# same51-dev.net
KiCad netlist of a schematic drawn in EAGLE
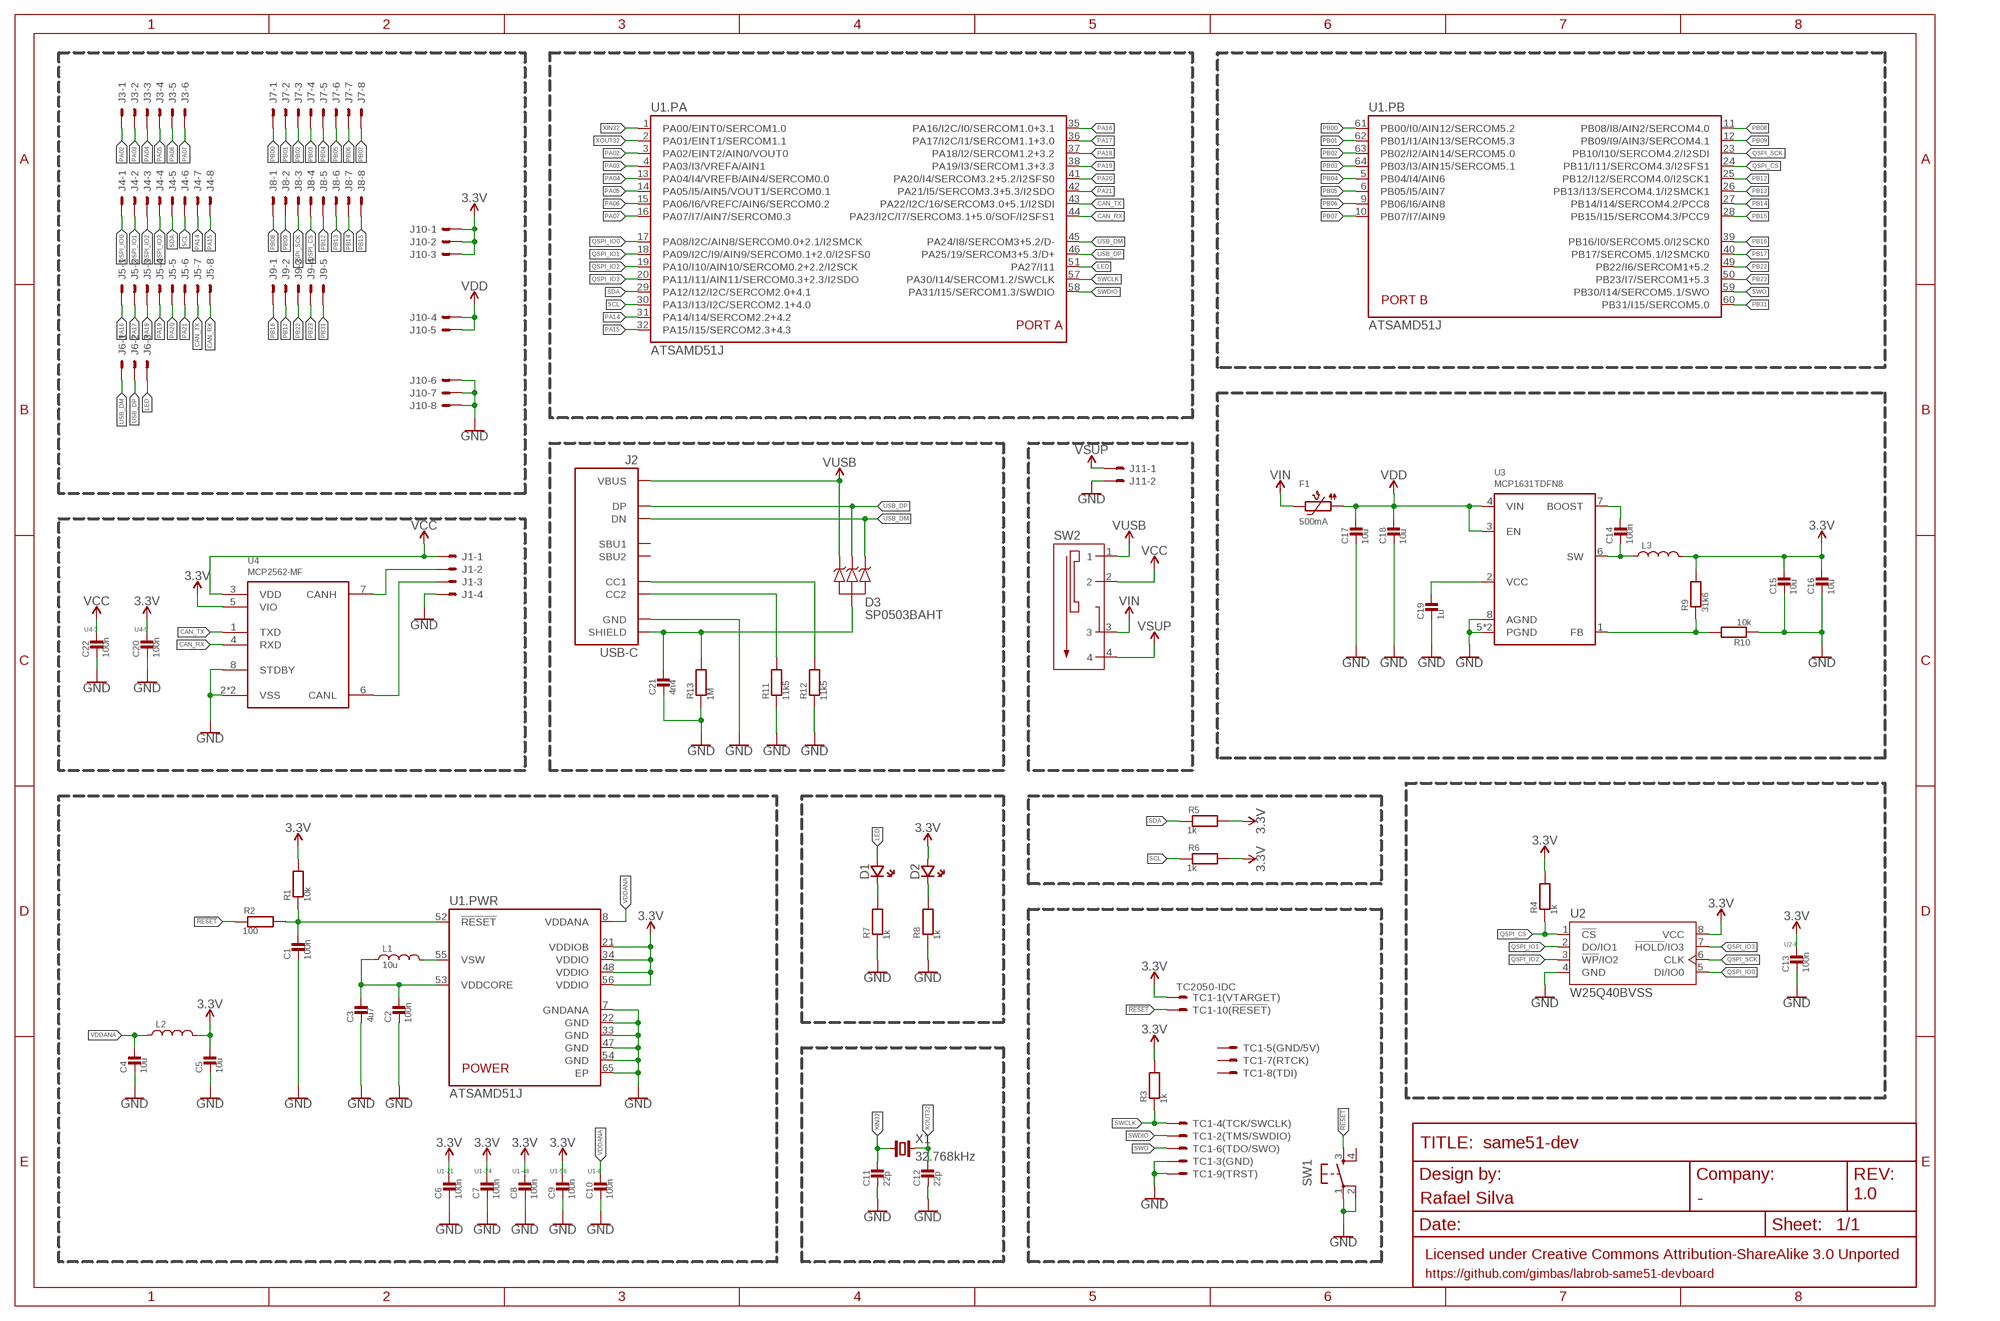
[diagram p0: schematic, sheet 1]

(export (version "E")
  (design (tool "Eeschema 10.0.6"))
  (components
    (comp (ref "C1")
      (value "100n")
      (footprint "eagle-import:0603_WAVE")
      (libsource (lib "eagle-import") (part "MLCC0603"))
    )
    (comp (ref "C2")
      (value "100n")
      (footprint "eagle-import:0603_WAVE")
      (libsource (lib "eagle-import") (part "MLCC0603"))
    )
    (comp (ref "C3")
      (value "4u7")
      (footprint "eagle-import:0603_WAVE")
      (libsource (lib "eagle-import") (part "MLCC0603"))
    )
    (comp (ref "C4")
      (value "10u")
      (footprint "eagle-import:0603_WAVE")
      (libsource (lib "eagle-import") (part "MLCC0603"))
    )
    (comp (ref "C5")
      (value "10u")
      (footprint "eagle-import:0603_WAVE")
      (libsource (lib "eagle-import") (part "MLCC0603"))
    )
    (comp (ref "C6")
      (value "100n")
      (footprint "eagle-import:0603_WAVE")
      (libsource (lib "eagle-import") (part "MLCC0603"))
    )
    (comp (ref "C7")
      (value "100n")
      (footprint "eagle-import:0603_WAVE")
      (libsource (lib "eagle-import") (part "MLCC0603"))
    )
    (comp (ref "C8")
      (value "100n")
      (footprint "eagle-import:0603_WAVE")
      (libsource (lib "eagle-import") (part "MLCC0603"))
    )
    (comp (ref "C9")
      (value "100n")
      (footprint "eagle-import:0603_WAVE")
      (libsource (lib "eagle-import") (part "MLCC0603"))
    )
    (comp (ref "C10")
      (value "100n")
      (footprint "eagle-import:0603_WAVE")
      (libsource (lib "eagle-import") (part "MLCC0603"))
    )
    (comp (ref "C11")
      (value "22p")
      (footprint "eagle-import:0603_WAVE")
      (libsource (lib "eagle-import") (part "MLCC0603"))
    )
    (comp (ref "C12")
      (value "22p")
      (footprint "eagle-import:0603_WAVE")
      (libsource (lib "eagle-import") (part "MLCC0603"))
    )
    (comp (ref "C13")
      (value "100n")
      (footprint "eagle-import:0603_WAVE")
      (libsource (lib "eagle-import") (part "MLCC0603"))
    )
    (comp (ref "C14")
      (value "100n")
      (footprint "eagle-import:0603_WAVE")
      (libsource (lib "eagle-import") (part "MLCC0603"))
    )
    (comp (ref "C15")
      (value "10u")
      (footprint "eagle-import:0603_WAVE")
      (libsource (lib "eagle-import") (part "MLCC0603"))
    )
    (comp (ref "C16")
      (value "10u")
      (footprint "eagle-import:0603_WAVE")
      (libsource (lib "eagle-import") (part "MLCC0603"))
    )
    (comp (ref "C17")
      (value "10u")
      (footprint "eagle-import:0603_WAVE")
      (libsource (lib "eagle-import") (part "MLCC0603"))
    )
    (comp (ref "C18")
      (value "10u")
      (footprint "eagle-import:0603_WAVE")
      (libsource (lib "eagle-import") (part "MLCC0603"))
    )
    (comp (ref "C19")
      (value "1u")
      (footprint "eagle-import:0603_WAVE")
      (libsource (lib "eagle-import") (part "MLCC0603"))
    )
    (comp (ref "C20")
      (value "100n")
      (footprint "eagle-import:0603_WAVE")
      (libsource (lib "eagle-import") (part "MLCC0603"))
    )
    (comp (ref "C21")
      (value "4n4")
      (footprint "eagle-import:0603_WAVE")
      (libsource (lib "eagle-import") (part "MLCC0603"))
    )
    (comp (ref "C22")
      (value "100n")
      (footprint "eagle-import:0603_WAVE")
      (libsource (lib "eagle-import") (part "MLCC0603"))
    )
    (comp (ref "D1")
      (value "LED0603")
      (footprint "eagle-import:CHIPLED_0603")
      (libsource (lib "eagle-import") (part "LED0603"))
    )
    (comp (ref "D2")
      (value "LED0603")
      (footprint "eagle-import:CHIPLED_0603")
      (libsource (lib "eagle-import") (part "LED0603"))
    )
    (comp (ref "D3")
      (value "SP0503BAHT")
      (footprint "eagle-import:SOT143")
      (libsource (lib "eagle-import") (part "SP0503BAHT"))
    )
    (comp (ref "F1")
      (value "500mA")
      (footprint "eagle-import:0805")
      (libsource (lib "eagle-import") (part "PTC0805"))
    )
    (comp (ref "J1")
      (value "4")
      (footprint "eagle-import:1X4_2.54")
      (libsource (lib "eagle-import") (part "4"))
    )
    (comp (ref "J2")
      (value "USB-C")
      (footprint "eagle-import:USB-C")
      (libsource (lib "eagle-import") (part "USB-C"))
    )
    (comp (ref "J3")
      (value "6")
      (footprint "eagle-import:1X6_2.54")
      (libsource (lib "eagle-import") (part "6"))
    )
    (comp (ref "J4")
      (value "8")
      (footprint "eagle-import:1X8_2.54")
      (libsource (lib "eagle-import") (part "8"))
    )
    (comp (ref "J5")
      (value "8")
      (footprint "eagle-import:1X8_2.54")
      (libsource (lib "eagle-import") (part "8"))
    )
    (comp (ref "J6")
      (value "3")
      (footprint "eagle-import:1X3_2.54")
      (libsource (lib "eagle-import") (part "3"))
    )
    (comp (ref "J7")
      (value "8")
      (footprint "eagle-import:1X8_2.54")
      (libsource (lib "eagle-import") (part "8"))
    )
    (comp (ref "J8")
      (value "8")
      (footprint "eagle-import:1X8_2.54")
      (libsource (lib "eagle-import") (part "8"))
    )
    (comp (ref "J9")
      (value "5")
      (footprint "eagle-import:1X5_2.54")
      (libsource (lib "eagle-import") (part "5"))
    )
    (comp (ref "J10")
      (value "8")
      (footprint "eagle-import:1X8_2.54")
      (libsource (lib "eagle-import") (part "8"))
    )
    (comp (ref "J11")
      (value "2")
      (footprint "eagle-import:2X1_2.54")
      (libsource (lib "eagle-import") (part "2"))
    )
    (comp (ref "L1")
      (value "10u")
      (footprint "eagle-import:_0806")
      (libsource (lib "eagle-import") (part "INDUCTOR_NC_0806"))
    )
    (comp (ref "L2")
      (value "INDUCTOR_NC_0603")
      (footprint "eagle-import:_0603")
      (libsource (lib "eagle-import") (part "INDUCTOR_NC_0603"))
    )
    (comp (ref "L3")
      (value "INDUCTOR_NC_0806")
      (footprint "eagle-import:_0806")
      (libsource (lib "eagle-import") (part "INDUCTOR_NC_0806"))
    )
    (comp (ref "R1")
      (value "10k")
      (footprint "eagle-import:0603_WAVE")
      (libsource (lib "eagle-import") (part "RESISTOR0603"))
    )
    (comp (ref "R2")
      (value "100")
      (footprint "eagle-import:0603_WAVE")
      (libsource (lib "eagle-import") (part "RESISTOR0603"))
    )
    (comp (ref "R3")
      (value "1k")
      (footprint "eagle-import:0603_WAVE")
      (libsource (lib "eagle-import") (part "RESISTOR0603"))
    )
    (comp (ref "R4")
      (value "1k")
      (footprint "eagle-import:0603_WAVE")
      (libsource (lib "eagle-import") (part "RESISTOR0603"))
    )
    (comp (ref "R5")
      (value "1k")
      (footprint "eagle-import:0603_WAVE")
      (libsource (lib "eagle-import") (part "RESISTOR0603"))
    )
    (comp (ref "R6")
      (value "1k")
      (footprint "eagle-import:0603_WAVE")
      (libsource (lib "eagle-import") (part "RESISTOR0603"))
    )
    (comp (ref "R7")
      (value "1k")
      (footprint "eagle-import:0603_WAVE")
      (libsource (lib "eagle-import") (part "RESISTOR0603"))
    )
    (comp (ref "R8")
      (value "1k")
      (footprint "eagle-import:0603_WAVE")
      (libsource (lib "eagle-import") (part "RESISTOR0603"))
    )
    (comp (ref "R9")
      (value "31k6")
      (footprint "eagle-import:0603_WAVE")
      (libsource (lib "eagle-import") (part "RESISTOR0603"))
    )
    (comp (ref "R10")
      (value "10k")
      (footprint "eagle-import:0603_WAVE")
      (libsource (lib "eagle-import") (part "RESISTOR0603"))
    )
    (comp (ref "R11")
      (value "11k5")
      (footprint "eagle-import:0603_WAVE")
      (libsource (lib "eagle-import") (part "RESISTOR0603"))
    )
    (comp (ref "R12")
      (value "11k5")
      (footprint "eagle-import:0603_WAVE")
      (libsource (lib "eagle-import") (part "RESISTOR0603"))
    )
    (comp (ref "R13")
      (value "1M")
      (footprint "eagle-import:0603_WAVE")
      (libsource (lib "eagle-import") (part "RESISTOR0603"))
    )
    (comp (ref "SW1")
      (value "PUSH_BUTTON3X4X2")
      (footprint "eagle-import:3X4X2")
      (libsource (lib "eagle-import") (part "PUSH_BUTTON3X4X2"))
    )
    (comp (ref "SW2")
      (value "MSK-13C01")
      (footprint "eagle-import:MSK-13C01")
      (libsource (lib "eagle-import") (part "MSK-13C01"))
    )
    (comp (ref "TC1")
      (value "TC2050-IDC")
      (footprint "eagle-import:TC2050-IDC")
      (libsource (lib "eagle-import") (part "TC2050-IDC"))
    )
    (comp (ref "U1")
      (value "ATSAMD51J")
      (footprint "eagle-import:VQFN64")
      (libsource (lib "eagle-import") (part "ATSAMD51J"))
    )
    (comp (ref "U2")
      (value "W25Q40BVSS")
      (footprint "eagle-import:SO08-SS")
      (libsource (lib "eagle-import") (part "W25Q40BVSS"))
    )
    (comp (ref "U3")
      (value "MCP1631TDFN8")
      (footprint "eagle-import:TDFN8")
      (libsource (lib "eagle-import") (part "MCP1631TDFN8"))
    )
    (comp (ref "U4")
      (value "MCP2562-MF")
      (footprint "eagle-import:DFN8")
      (libsource (lib "eagle-import") (part "MCP2562-MF"))
    )
    (comp (ref "X1")
      (value "32.768kHz")
      (footprint "eagle-import:2-SMD-3215")
      (libsource (lib "eagle-import") (part "CRYSTAL2-SMD-3215"))
    )
  )
  (nets
    (net (code "1") (name "/~{RESET}") (class "Default")
      (node (ref "R2") (pin "P$1") (pinfunction "P$1_P$1") (pintype "bidirectional"))
      (node (ref "SW1") (pin "3") (pinfunction "4_3") (pintype "passive"))
      (node (ref "TC1") (pin "10") (pinfunction "S_10") (pintype "passive"))
    )
    (net (code "2") (name "3.3V") (class "Default")
      (node (ref "C13") (pin "P$1") (pinfunction "P$1_P$1") (pintype "bidirectional"))
      (node (ref "C15") (pin "P$1") (pinfunction "P$1_P$1") (pintype "bidirectional"))
      (node (ref "C16") (pin "P$1") (pinfunction "P$1_P$1") (pintype "bidirectional"))
      (node (ref "C20") (pin "P$1") (pinfunction "P$1_P$1") (pintype "bidirectional"))
      (node (ref "C5") (pin "P$1") (pinfunction "P$1_P$1") (pintype "bidirectional"))
      (node (ref "C6") (pin "P$1") (pinfunction "P$1_P$1") (pintype "bidirectional"))
      (node (ref "C7") (pin "P$1") (pinfunction "P$1_P$1") (pintype "bidirectional"))
      (node (ref "C8") (pin "P$1") (pinfunction "P$1_P$1") (pintype "bidirectional"))
      (node (ref "C9") (pin "P$1") (pinfunction "P$1_P$1") (pintype "bidirectional"))
      (node (ref "D2") (pin "A") (pinfunction "AN_A") (pintype "bidirectional"))
      (node (ref "J10") (pin "1") (pinfunction "S_1") (pintype "passive"))
      (node (ref "J10") (pin "2") (pinfunction "S_2") (pintype "passive"))
      (node (ref "J10") (pin "3") (pinfunction "S_3") (pintype "passive"))
      (node (ref "L2") (pin "2") (pinfunction "P$2_2") (pintype "bidirectional"))
      (node (ref "L3") (pin "2") (pinfunction "P$2_2") (pintype "bidirectional"))
      (node (ref "R1") (pin "P$2") (pinfunction "P$2_P$2") (pintype "bidirectional"))
      (node (ref "R3") (pin "P$2") (pinfunction "P$2_P$2") (pintype "bidirectional"))
      (node (ref "R4") (pin "P$2") (pinfunction "P$2_P$2") (pintype "bidirectional"))
      (node (ref "R5") (pin "P$2") (pinfunction "P$2_P$2") (pintype "bidirectional"))
      (node (ref "R6") (pin "P$2") (pinfunction "P$2_P$2") (pintype "bidirectional"))
      (node (ref "R9") (pin "P$2") (pinfunction "P$2_P$2") (pintype "bidirectional"))
      (node (ref "TC1") (pin "1") (pinfunction "S_1") (pintype "passive"))
      (node (ref "U1") (pin "21") (pinfunction "VDDIOB_21") (pintype "bidirectional"))
      (node (ref "U1") (pin "34") (pinfunction "VDDIO_34") (pintype "bidirectional"))
      (node (ref "U1") (pin "48") (pinfunction "VDDIO_48") (pintype "bidirectional"))
      (node (ref "U1") (pin "56") (pinfunction "VDDIO_56") (pintype "bidirectional"))
      (node (ref "U2") (pin "8") (pinfunction "VCC_8") (pintype "power_in"))
      (node (ref "U4") (pin "5") (pinfunction "VIO_5") (pintype "power_in"))
    )
    (net (code "3") (name "CAN_RX") (class "Default")
      (node (ref "J5") (pin "8") (pinfunction "S_8") (pintype "passive"))
      (node (ref "U1") (pin "44") (pinfunction "PA23/I2C/I7/SERCOM3.1+5.0/SOF/I2SFS1_44") (pintype "bidirectional"))
      (node (ref "U4") (pin "4") (pinfunction "RXD_4") (pintype "bidirectional"))
    )
    (net (code "4") (name "CAN_TX") (class "Default")
      (node (ref "J5") (pin "7") (pinfunction "S_7") (pintype "passive"))
      (node (ref "U1") (pin "43") (pinfunction "PA22/I2C/16/SERCOM3.0+5.1/I2SDI_43") (pintype "bidirectional"))
      (node (ref "U4") (pin "1") (pinfunction "TXD_1") (pintype "bidirectional"))
    )
    (net (code "5") (name "GND") (class "Default")
      (node (ref "C1") (pin "P$2") (pinfunction "P$2_P$2") (pintype "bidirectional"))
      (node (ref "C10") (pin "P$2") (pinfunction "P$2_P$2") (pintype "bidirectional"))
      (node (ref "C11") (pin "P$2") (pinfunction "P$2_P$2") (pintype "bidirectional"))
      (node (ref "C12") (pin "P$2") (pinfunction "P$2_P$2") (pintype "bidirectional"))
      (node (ref "C13") (pin "P$2") (pinfunction "P$2_P$2") (pintype "bidirectional"))
      (node (ref "C15") (pin "P$2") (pinfunction "P$2_P$2") (pintype "bidirectional"))
      (node (ref "C16") (pin "P$2") (pinfunction "P$2_P$2") (pintype "bidirectional"))
      (node (ref "C17") (pin "P$2") (pinfunction "P$2_P$2") (pintype "bidirectional"))
      (node (ref "C18") (pin "P$2") (pinfunction "P$2_P$2") (pintype "bidirectional"))
      (node (ref "C19") (pin "P$2") (pinfunction "P$2_P$2") (pintype "bidirectional"))
      (node (ref "C2") (pin "P$2") (pinfunction "P$2_P$2") (pintype "bidirectional"))
      (node (ref "C20") (pin "P$2") (pinfunction "P$2_P$2") (pintype "bidirectional"))
      (node (ref "C21") (pin "P$2") (pinfunction "P$2_P$2") (pintype "bidirectional"))
      (node (ref "C22") (pin "P$2") (pinfunction "P$2_P$2") (pintype "bidirectional"))
      (node (ref "C3") (pin "P$2") (pinfunction "P$2_P$2") (pintype "bidirectional"))
      (node (ref "C4") (pin "P$2") (pinfunction "P$2_P$2") (pintype "bidirectional"))
      (node (ref "C5") (pin "P$2") (pinfunction "P$2_P$2") (pintype "bidirectional"))
      (node (ref "C6") (pin "P$2") (pinfunction "P$2_P$2") (pintype "bidirectional"))
      (node (ref "C7") (pin "P$2") (pinfunction "P$2_P$2") (pintype "bidirectional"))
      (node (ref "C8") (pin "P$2") (pinfunction "P$2_P$2") (pintype "bidirectional"))
      (node (ref "C9") (pin "P$2") (pinfunction "P$2_P$2") (pintype "bidirectional"))
      (node (ref "J1") (pin "4") (pinfunction "S_4") (pintype "passive"))
      (node (ref "J10") (pin "6") (pinfunction "S_6") (pintype "passive"))
      (node (ref "J10") (pin "7") (pinfunction "S_7") (pintype "passive"))
      (node (ref "J10") (pin "8") (pinfunction "S_8") (pintype "passive"))
      (node (ref "J11") (pin "2") (pinfunction "S_2") (pintype "passive"))
      (node (ref "J2") (pin "A1/B12") (pinfunction "GND_A1/B12") (pintype "bidirectional"))
      (node (ref "J2") (pin "B1/A12") (pinfunction "GND_B1/A12") (pintype "bidirectional"))
      (node (ref "R10") (pin "P$1") (pinfunction "P$1_P$1") (pintype "bidirectional"))
      (node (ref "R11") (pin "P$1") (pinfunction "P$1_P$1") (pintype "bidirectional"))
      (node (ref "R12") (pin "P$1") (pinfunction "P$1_P$1") (pintype "bidirectional"))
      (node (ref "R13") (pin "P$1") (pinfunction "P$1_P$1") (pintype "bidirectional"))
      (node (ref "R7") (pin "P$1") (pinfunction "P$1_P$1") (pintype "bidirectional"))
      (node (ref "R8") (pin "P$1") (pinfunction "P$1_P$1") (pintype "bidirectional"))
      (node (ref "SW1") (pin "1") (pinfunction "1_1") (pintype "passive"))
      (node (ref "SW1") (pin "2") (pinfunction "2_2") (pintype "passive"))
      (node (ref "TC1") (pin "3") (pinfunction "S_3") (pintype "passive"))
      (node (ref "TC1") (pin "9") (pinfunction "S_9") (pintype "passive"))
      (node (ref "U1") (pin "22") (pinfunction "GND_22") (pintype "bidirectional"))
      (node (ref "U1") (pin "33") (pinfunction "GND_33") (pintype "bidirectional"))
      (node (ref "U1") (pin "47") (pinfunction "GND_47") (pintype "bidirectional"))
      (node (ref "U1") (pin "54") (pinfunction "GND_54") (pintype "bidirectional"))
      (node (ref "U1") (pin "65") (pinfunction "EP_65") (pintype "bidirectional"))
      (node (ref "U1") (pin "7") (pinfunction "GNDANA_7") (pintype "bidirectional"))
      (node (ref "U2") (pin "4") (pinfunction "GND_4") (pintype "power_in"))
      (node (ref "U3") (pin "5") (pinfunction "PGND_5") (pintype "bidirectional"))
      (node (ref "U3") (pin "8") (pinfunction "AGND_8") (pintype "bidirectional"))
      (node (ref "U3") (pin "9") (pinfunction "PGND_9") (pintype "bidirectional"))
      (node (ref "U4") (pin "2") (pinfunction "VSS_2") (pintype "power_in"))
      (node (ref "U4") (pin "8") (pinfunction "STDBY_8") (pintype "bidirectional"))
      (node (ref "U4") (pin "9") (pinfunction "VSS_9") (pintype "power_in"))
    )
    (net (code "6") (name "LED") (class "Default")
      (node (ref "D1") (pin "A") (pinfunction "AN_A") (pintype "bidirectional"))
      (node (ref "J6") (pin "3") (pinfunction "S_3") (pintype "passive"))
      (node (ref "U1") (pin "51") (pinfunction "PA27/I11_51") (pintype "bidirectional"))
    )
    (net (code "7") (name "Net-(C21-PadP$1)") (class "Default")
      (node (ref "C21") (pin "P$1") (pinfunction "P$1_P$1") (pintype "bidirectional"))
      (node (ref "D3") (pin "1") (pinfunction "1_1") (pintype "bidirectional"))
      (node (ref "J2") (pin "SHIELD0") (pinfunction "SHIELD_SHIELD0") (pintype "bidirectional"))
      (node (ref "J2") (pin "SHIELD1") (pinfunction "SHIELD_SHIELD1") (pintype "bidirectional"))
      (node (ref "J2") (pin "SHIELD2") (pinfunction "SHIELD_SHIELD2") (pintype "bidirectional"))
      (node (ref "J2") (pin "SHIELD3") (pinfunction "SHIELD_SHIELD3") (pintype "bidirectional"))
      (node (ref "R13") (pin "P$2") (pinfunction "P$2_P$2") (pintype "bidirectional"))
    )
    (net (code "8") (name "Net-(D1-CA)") (class "Default")
      (node (ref "D1") (pin "C") (pinfunction "CA_C") (pintype "bidirectional"))
      (node (ref "R7") (pin "P$2") (pinfunction "P$2_P$2") (pintype "bidirectional"))
    )
    (net (code "9") (name "Net-(D2-CA)") (class "Default")
      (node (ref "D2") (pin "C") (pinfunction "CA_C") (pintype "bidirectional"))
      (node (ref "R8") (pin "P$2") (pinfunction "P$2_P$2") (pintype "bidirectional"))
    )
    (net (code "10") (name "Net-(J1B-S)") (class "Default")
      (node (ref "J1") (pin "2") (pinfunction "S_2") (pintype "passive"))
      (node (ref "U4") (pin "7") (pinfunction "CANH_7") (pintype "bidirectional"))
    )
    (net (code "11") (name "Net-(J1C-S)") (class "Default")
      (node (ref "J1") (pin "3") (pinfunction "S_3") (pintype "passive"))
      (node (ref "U4") (pin "6") (pinfunction "CANL_6") (pintype "bidirectional"))
    )
    (net (code "12") (name "Net-(J2-CC1)") (class "Default")
      (node (ref "J2") (pin "A5") (pinfunction "CC1_A5") (pintype "bidirectional"))
      (node (ref "R12") (pin "P$2") (pinfunction "P$2_P$2") (pintype "bidirectional"))
    )
    (net (code "13") (name "Net-(J2-CC2)") (class "Default")
      (node (ref "J2") (pin "B5") (pinfunction "CC2_B5") (pintype "bidirectional"))
      (node (ref "R11") (pin "P$2") (pinfunction "P$2_P$2") (pintype "bidirectional"))
    )
    (net (code "14") (name "Net-(L1-P$1)") (class "Default")
      (node (ref "C2") (pin "P$1") (pinfunction "P$1_P$1") (pintype "bidirectional"))
      (node (ref "C3") (pin "P$1") (pinfunction "P$1_P$1") (pintype "bidirectional"))
      (node (ref "L1") (pin "1") (pinfunction "P$1_1") (pintype "bidirectional"))
      (node (ref "U1") (pin "53") (pinfunction "VDDCORE_53") (pintype "bidirectional"))
    )
    (net (code "15") (name "Net-(L1-P$2)") (class "Default")
      (node (ref "L1") (pin "2") (pinfunction "P$2_2") (pintype "bidirectional"))
      (node (ref "U1") (pin "55") (pinfunction "VSW_55") (pintype "bidirectional"))
    )
    (net (code "16") (name "Net-(L3-P$1)") (class "Default")
      (node (ref "C14") (pin "P$2") (pinfunction "P$2_P$2") (pintype "bidirectional"))
      (node (ref "L3") (pin "1") (pinfunction "P$1_1") (pintype "bidirectional"))
      (node (ref "U3") (pin "6") (pinfunction "SW_6") (pintype "bidirectional"))
    )
    (net (code "17") (name "Net-(U1C-~{RESET})") (class "Default")
      (node (ref "C1") (pin "P$1") (pinfunction "P$1_P$1") (pintype "bidirectional"))
      (node (ref "R1") (pin "P$1") (pinfunction "P$1_P$1") (pintype "bidirectional"))
      (node (ref "R2") (pin "P$2") (pinfunction "P$2_P$2") (pintype "bidirectional"))
      (node (ref "U1") (pin "52") (pinfunction "~{RESET}_52") (pintype "bidirectional"))
    )
    (net (code "18") (name "Net-(U3-BOOST)") (class "Default")
      (node (ref "C14") (pin "P$1") (pinfunction "P$1_P$1") (pintype "bidirectional"))
      (node (ref "U3") (pin "7") (pinfunction "BOOST_7") (pintype "bidirectional"))
    )
    (net (code "19") (name "Net-(U3-FB)") (class "Default")
      (node (ref "R10") (pin "P$2") (pinfunction "P$2_P$2") (pintype "bidirectional"))
      (node (ref "R9") (pin "P$1") (pinfunction "P$1_P$1") (pintype "bidirectional"))
      (node (ref "U3") (pin "1") (pinfunction "FB_1") (pintype "bidirectional"))
    )
    (net (code "20") (name "Net-(U3-VCC)") (class "Default")
      (node (ref "C19") (pin "P$1") (pinfunction "P$1_P$1") (pintype "bidirectional"))
      (node (ref "U3") (pin "2") (pinfunction "VCC_2") (pintype "bidirectional"))
    )
    (net (code "21") (name "PA02") (class "Default")
      (node (ref "J3") (pin "1") (pinfunction "S_1") (pintype "passive"))
      (node (ref "U1") (pin "3") (pinfunction "PA02/EINT2/AIN0/VOUT0_3") (pintype "bidirectional"))
    )
    (net (code "22") (name "PA03") (class "Default")
      (node (ref "J3") (pin "2") (pinfunction "S_2") (pintype "passive"))
      (node (ref "U1") (pin "4") (pinfunction "PA03/I3/VREFA/AIN1_4") (pintype "bidirectional"))
    )
    (net (code "23") (name "PA04") (class "Default")
      (node (ref "J3") (pin "3") (pinfunction "S_3") (pintype "passive"))
      (node (ref "U1") (pin "13") (pinfunction "PA04/I4/VREFB/AIN4/SERCOM0.0_13") (pintype "bidirectional"))
    )
    (net (code "24") (name "PA05") (class "Default")
      (node (ref "J3") (pin "4") (pinfunction "S_4") (pintype "passive"))
      (node (ref "U1") (pin "14") (pinfunction "PA05/I5/AIN5/VOUT1/SERCOM0.1_14") (pintype "bidirectional"))
    )
    (net (code "25") (name "PA06") (class "Default")
      (node (ref "J3") (pin "5") (pinfunction "S_5") (pintype "passive"))
      (node (ref "U1") (pin "15") (pinfunction "PA06/I6/VREFC/AIN6/SERCOM0.2_15") (pintype "bidirectional"))
    )
    (net (code "26") (name "PA07") (class "Default")
      (node (ref "J3") (pin "6") (pinfunction "S_6") (pintype "passive"))
      (node (ref "U1") (pin "16") (pinfunction "PA07/I7/AIN7/SERCOM0.3_16") (pintype "bidirectional"))
    )
    (net (code "27") (name "PA14") (class "Default")
      (node (ref "J4") (pin "7") (pinfunction "S_7") (pintype "passive"))
      (node (ref "U1") (pin "31") (pinfunction "PA14/I14/SERCOM2.2+4.2_31") (pintype "bidirectional"))
    )
    (net (code "28") (name "PA15") (class "Default")
      (node (ref "J4") (pin "8") (pinfunction "S_8") (pintype "passive"))
      (node (ref "U1") (pin "32") (pinfunction "PA15/I15/SERCOM2.3+4.3_32") (pintype "bidirectional"))
    )
    (net (code "29") (name "PA16") (class "Default")
      (node (ref "J5") (pin "1") (pinfunction "S_1") (pintype "passive"))
      (node (ref "U1") (pin "35") (pinfunction "PA16/I2C/I0/SERCOM1.0+3.1_35") (pintype "bidirectional"))
    )
    (net (code "30") (name "PA17") (class "Default")
      (node (ref "J5") (pin "2") (pinfunction "S_2") (pintype "passive"))
      (node (ref "U1") (pin "36") (pinfunction "PA17/I2C/I1/SERCOM1.1+3.0_36") (pintype "bidirectional"))
    )
    (net (code "31") (name "PA18") (class "Default")
      (node (ref "J5") (pin "3") (pinfunction "S_3") (pintype "passive"))
      (node (ref "U1") (pin "37") (pinfunction "PA18/I2/SERCOM1.2+3.2_37") (pintype "bidirectional"))
    )
    (net (code "32") (name "PA19") (class "Default")
      (node (ref "J5") (pin "4") (pinfunction "S_4") (pintype "passive"))
      (node (ref "U1") (pin "38") (pinfunction "PA19/I3/SERCOM1.3+3.3_38") (pintype "bidirectional"))
    )
    (net (code "33") (name "PA20") (class "Default")
      (node (ref "J5") (pin "5") (pinfunction "S_5") (pintype "passive"))
      (node (ref "U1") (pin "41") (pinfunction "PA20/I4/SERCOM3.2+5.2/I2SFS0_41") (pintype "bidirectional"))
    )
    (net (code "34") (name "PA21") (class "Default")
      (node (ref "J5") (pin "6") (pinfunction "S_6") (pintype "passive"))
      (node (ref "U1") (pin "42") (pinfunction "PA21/I5/SERCOM3.3+5.3/I2SDO_42") (pintype "bidirectional"))
    )
    (net (code "35") (name "PB00") (class "Default")
      (node (ref "J7") (pin "1") (pinfunction "S_1") (pintype "passive"))
      (node (ref "U1") (pin "61") (pinfunction "PB00/I0/AIN12/SERCOM5.2_61") (pintype "bidirectional"))
    )
    (net (code "36") (name "PB01") (class "Default")
      (node (ref "J7") (pin "2") (pinfunction "S_2") (pintype "passive"))
      (node (ref "U1") (pin "62") (pinfunction "PB01/I1/AIN13/SERCOM5.3_62") (pintype "bidirectional"))
    )
    (net (code "37") (name "PB02") (class "Default")
      (node (ref "J7") (pin "3") (pinfunction "S_3") (pintype "passive"))
      (node (ref "U1") (pin "63") (pinfunction "PB02/I2/AIN14/SERCOM5.0_63") (pintype "bidirectional"))
    )
    (net (code "38") (name "PB03") (class "Default")
      (node (ref "J7") (pin "4") (pinfunction "S_4") (pintype "passive"))
      (node (ref "U1") (pin "64") (pinfunction "PB03/I3/AIN15/SERCOM5.1_64") (pintype "bidirectional"))
    )
    (net (code "39") (name "PB04") (class "Default")
      (node (ref "J7") (pin "5") (pinfunction "S_5") (pintype "passive"))
      (node (ref "U1") (pin "5") (pinfunction "PB04/I4/AIN6_5") (pintype "bidirectional"))
    )
    (net (code "40") (name "PB05") (class "Default")
      (node (ref "J7") (pin "6") (pinfunction "S_6") (pintype "passive"))
      (node (ref "U1") (pin "6") (pinfunction "PB05/I5/AIN7_6") (pintype "bidirectional"))
    )
    (net (code "41") (name "PB06") (class "Default")
      (node (ref "J7") (pin "7") (pinfunction "S_7") (pintype "passive"))
      (node (ref "U1") (pin "9") (pinfunction "PB06/I6/AIN8_9") (pintype "bidirectional"))
    )
    (net (code "42") (name "PB07") (class "Default")
      (node (ref "J7") (pin "8") (pinfunction "S_8") (pintype "passive"))
      (node (ref "U1") (pin "10") (pinfunction "PB07/I7/AIN9_10") (pintype "bidirectional"))
    )
    (net (code "43") (name "PB08") (class "Default")
      (node (ref "J8") (pin "1") (pinfunction "S_1") (pintype "passive"))
      (node (ref "U1") (pin "11") (pinfunction "PB08/I8/AIN2/SERCOM4.0_11") (pintype "bidirectional"))
    )
    (net (code "44") (name "PB09") (class "Default")
      (node (ref "J8") (pin "2") (pinfunction "S_2") (pintype "passive"))
      (node (ref "U1") (pin "12") (pinfunction "PB09/I9/AIN3/SERCOM4.1_12") (pintype "bidirectional"))
    )
    (net (code "45") (name "PB12") (class "Default")
      (node (ref "J8") (pin "5") (pinfunction "S_5") (pintype "passive"))
      (node (ref "U1") (pin "25") (pinfunction "PB12/I12/SERCOM4.0/I2SCK1_25") (pintype "bidirectional"))
    )
    (net (code "46") (name "PB13") (class "Default")
      (node (ref "J8") (pin "6") (pinfunction "S_6") (pintype "passive"))
      (node (ref "U1") (pin "26") (pinfunction "PB13/I13/SERCOM4.1/I2SMCK1_26") (pintype "bidirectional"))
    )
    (net (code "47") (name "PB14") (class "Default")
      (node (ref "J8") (pin "7") (pinfunction "S_7") (pintype "passive"))
      (node (ref "U1") (pin "27") (pinfunction "PB14/I14/SERCOM4.2/PCC8_27") (pintype "bidirectional"))
    )
    (net (code "48") (name "PB15") (class "Default")
      (node (ref "J8") (pin "8") (pinfunction "S_8") (pintype "passive"))
      (node (ref "U1") (pin "28") (pinfunction "PB15/I15/SERCOM4.3/PCC9_28") (pintype "bidirectional"))
    )
    (net (code "49") (name "PB16") (class "Default")
      (node (ref "J9") (pin "1") (pinfunction "S_1") (pintype "passive"))
      (node (ref "U1") (pin "39") (pinfunction "PB16/I0/SERCOM5.0/I2SCK0_39") (pintype "bidirectional"))
    )
    (net (code "50") (name "PB17") (class "Default")
      (node (ref "J9") (pin "2") (pinfunction "S_2") (pintype "passive"))
      (node (ref "U1") (pin "40") (pinfunction "PB17/SERCOM5.1/I2SMCK0_40") (pintype "bidirectional"))
    )
    (net (code "51") (name "PB22") (class "Default")
      (node (ref "J9") (pin "3") (pinfunction "S_3") (pintype "passive"))
      (node (ref "U1") (pin "49") (pinfunction "PB22/I6/SERCOM1+5.2_49") (pintype "bidirectional"))
    )
    (net (code "52") (name "PB23") (class "Default")
      (node (ref "J9") (pin "4") (pinfunction "S_4") (pintype "passive"))
      (node (ref "U1") (pin "50") (pinfunction "PB23/I7/SERCOM1+5.3_50") (pintype "bidirectional"))
    )
    (net (code "53") (name "PB31") (class "Default")
      (node (ref "J9") (pin "5") (pinfunction "S_5") (pintype "passive"))
      (node (ref "U1") (pin "60") (pinfunction "PB31/I15/SERCOM5.0_60") (pintype "bidirectional"))
    )
    (net (code "54") (name "QSPI_CS") (class "Default")
      (node (ref "J8") (pin "4") (pinfunction "S_4") (pintype "passive"))
      (node (ref "R4") (pin "P$1") (pinfunction "P$1_P$1") (pintype "bidirectional"))
      (node (ref "U1") (pin "24") (pinfunction "PB11/I11/SERCOM4.3/I2SFS1_24") (pintype "bidirectional"))
      (node (ref "U2") (pin "1") (pinfunction "~{CS}_1") (pintype "input"))
    )
    (net (code "55") (name "QSPI_IO0") (class "Default")
      (node (ref "J4") (pin "1") (pinfunction "S_1") (pintype "passive"))
      (node (ref "U1") (pin "17") (pinfunction "PA08/I2C/AIN8/SERCOM0.0+2.1/I2SMCK_17") (pintype "bidirectional"))
      (node (ref "U2") (pin "5") (pinfunction "DI/IO0_5") (pintype "input"))
    )
    (net (code "56") (name "QSPI_IO1") (class "Default")
      (node (ref "J4") (pin "2") (pinfunction "S_2") (pintype "passive"))
      (node (ref "U1") (pin "18") (pinfunction "PA09/I2C/I9/AIN9/SERCOM0.1+2.0/I2SFS0_18") (pintype "bidirectional"))
      (node (ref "U2") (pin "2") (pinfunction "DO/IO1_2") (pintype "output"))
    )
    (net (code "57") (name "QSPI_IO2") (class "Default")
      (node (ref "J4") (pin "3") (pinfunction "S_3") (pintype "passive"))
      (node (ref "U1") (pin "19") (pinfunction "PA10/I10/AIN10/SERCOM0.2+2.2/I2SCK_19") (pintype "bidirectional"))
      (node (ref "U2") (pin "3") (pinfunction "~{WP}/IO2_3") (pintype "input"))
    )
    (net (code "58") (name "QSPI_IO3") (class "Default")
      (node (ref "J4") (pin "4") (pinfunction "S_4") (pintype "passive"))
      (node (ref "U1") (pin "20") (pinfunction "PA11/I11/AIN11/SERCOM0.3+2.3/I2SDO_20") (pintype "bidirectional"))
      (node (ref "U2") (pin "7") (pinfunction "~{HOLD}/IO3_7") (pintype "input"))
    )
    (net (code "59") (name "QSPI_SCK") (class "Default")
      (node (ref "J8") (pin "3") (pinfunction "S_3") (pintype "passive"))
      (node (ref "U1") (pin "23") (pinfunction "PB10/I10/SERCOM4.2/I2SDI_23") (pintype "bidirectional"))
      (node (ref "U2") (pin "6") (pinfunction "CLK_6") (pintype "input"))
    )
    (net (code "60") (name "SCL") (class "Default")
      (node (ref "J4") (pin "6") (pinfunction "S_6") (pintype "passive"))
      (node (ref "R6") (pin "P$1") (pinfunction "P$1_P$1") (pintype "bidirectional"))
      (node (ref "U1") (pin "30") (pinfunction "PA13/I13/I2C/SERCOM2.1+4.0_30") (pintype "bidirectional"))
    )
    (net (code "61") (name "SDA") (class "Default")
      (node (ref "J4") (pin "5") (pinfunction "S_5") (pintype "passive"))
      (node (ref "R5") (pin "P$1") (pinfunction "P$1_P$1") (pintype "bidirectional"))
      (node (ref "U1") (pin "29") (pinfunction "PA12/I12/I2C/SERCOM2.0+4.1_29") (pintype "bidirectional"))
    )
    (net (code "62") (name "SWCLK") (class "Default")
      (node (ref "R3") (pin "P$1") (pinfunction "P$1_P$1") (pintype "bidirectional"))
      (node (ref "TC1") (pin "4") (pinfunction "S_4") (pintype "passive"))
      (node (ref "U1") (pin "57") (pinfunction "PA30/I14/SERCOM1.2/SWCLK_57") (pintype "bidirectional"))
    )
    (net (code "63") (name "SWDIO") (class "Default")
      (node (ref "TC1") (pin "2") (pinfunction "S_2") (pintype "passive"))
      (node (ref "U1") (pin "58") (pinfunction "PA31/I15/SERCOM1.3/SWDIO_58") (pintype "bidirectional"))
    )
    (net (code "64") (name "SWO") (class "Default")
      (node (ref "TC1") (pin "6") (pinfunction "S_6") (pintype "passive"))
      (node (ref "U1") (pin "59") (pinfunction "PB30/I14/SERCOM5.1/SWO_59") (pintype "bidirectional"))
    )
    (net (code "65") (name "USB_DM") (class "Default")
      (node (ref "D3") (pin "4") (pinfunction "4_4") (pintype "bidirectional"))
      (node (ref "J2") (pin "A7") (pinfunction "DN_A7") (pintype "bidirectional"))
      (node (ref "J2") (pin "B7") (pinfunction "DN_B7") (pintype "bidirectional"))
      (node (ref "J6") (pin "1") (pinfunction "S_1") (pintype "passive"))
      (node (ref "U1") (pin "45") (pinfunction "PA24/I8/SERCOM3+5.2/D-_45") (pintype "bidirectional"))
    )
    (net (code "66") (name "USB_DP") (class "Default")
      (node (ref "D3") (pin "3") (pinfunction "3_3") (pintype "bidirectional"))
      (node (ref "J2") (pin "A6") (pinfunction "DP_A6") (pintype "bidirectional"))
      (node (ref "J2") (pin "B6") (pinfunction "DP_B6") (pintype "bidirectional"))
      (node (ref "J6") (pin "2") (pinfunction "S_2") (pintype "passive"))
      (node (ref "U1") (pin "46") (pinfunction "PA25/19/SERCOM3+5.3/D+_46") (pintype "bidirectional"))
    )
    (net (code "67") (name "VCC") (class "Default")
      (node (ref "C22") (pin "P$1") (pinfunction "P$1_P$1") (pintype "bidirectional"))
      (node (ref "J1") (pin "1") (pinfunction "S_1") (pintype "passive"))
      (node (ref "SW2") (pin "2") (pinfunction "2_2") (pintype "bidirectional"))
      (node (ref "U4") (pin "3") (pinfunction "VDD_3") (pintype "power_in"))
    )
    (net (code "68") (name "VDD") (class "Default")
      (node (ref "C17") (pin "P$1") (pinfunction "P$1_P$1") (pintype "bidirectional"))
      (node (ref "C18") (pin "P$1") (pinfunction "P$1_P$1") (pintype "bidirectional"))
      (node (ref "F1") (pin "1") (pinfunction "1_1") (pintype "passive"))
      (node (ref "J10") (pin "4") (pinfunction "S_4") (pintype "passive"))
      (node (ref "J10") (pin "5") (pinfunction "S_5") (pintype "passive"))
      (node (ref "U3") (pin "3") (pinfunction "EN_3") (pintype "bidirectional"))
      (node (ref "U3") (pin "4") (pinfunction "VIN_4") (pintype "bidirectional"))
    )
    (net (code "69") (name "VDDANA") (class "Default")
      (node (ref "C10") (pin "P$1") (pinfunction "P$1_P$1") (pintype "bidirectional"))
      (node (ref "C4") (pin "P$1") (pinfunction "P$1_P$1") (pintype "bidirectional"))
      (node (ref "L2") (pin "1") (pinfunction "P$1_1") (pintype "bidirectional"))
      (node (ref "U1") (pin "8") (pinfunction "VDDANA_8") (pintype "bidirectional"))
    )
    (net (code "70") (name "VIN") (class "Default")
      (node (ref "F1") (pin "2") (pinfunction "2_2") (pintype "passive"))
      (node (ref "SW2") (pin "3") (pinfunction "3_3") (pintype "bidirectional"))
    )
    (net (code "71") (name "VSUP") (class "Default")
      (node (ref "J11") (pin "1") (pinfunction "S_1") (pintype "passive"))
      (node (ref "SW2") (pin "4") (pinfunction "4_4") (pintype "bidirectional"))
    )
    (net (code "72") (name "VUSB") (class "Default")
      (node (ref "D3") (pin "2") (pinfunction "2_2") (pintype "bidirectional"))
      (node (ref "J2") (pin "A4/B9") (pinfunction "VBUS_A4/B9") (pintype "bidirectional"))
      (node (ref "J2") (pin "B4/A9") (pinfunction "VBUS_B4/A9") (pintype "bidirectional"))
      (node (ref "SW2") (pin "1") (pinfunction "1_1") (pintype "bidirectional"))
    )
    (net (code "73") (name "XIN32") (class "Default")
      (node (ref "C11") (pin "P$1") (pinfunction "P$1_P$1") (pintype "bidirectional"))
      (node (ref "U1") (pin "1") (pinfunction "PA00/EINT0/SERCOM1.0_1") (pintype "bidirectional"))
      (node (ref "X1") (pin "1") (pinfunction "1_1") (pintype "passive"))
    )
    (net (code "74") (name "XOUT32") (class "Default")
      (node (ref "C12") (pin "P$1") (pinfunction "P$1_P$1") (pintype "bidirectional"))
      (node (ref "U1") (pin "2") (pinfunction "PA01/EINT1/SERCOM1.1_2") (pintype "bidirectional"))
      (node (ref "X1") (pin "2") (pinfunction "2_2") (pintype "passive"))
    )
    (net (code "75") (name "unconnected-(J2-SBU1-PadA8)") (class "Default")
      (node (ref "J2") (pin "A8") (pinfunction "SBU1_A8") (pintype "bidirectional"))
    )
    (net (code "76") (name "unconnected-(J2-SBU2-PadB8)") (class "Default")
      (node (ref "J2") (pin "B8") (pinfunction "SBU2_B8") (pintype "bidirectional"))
    )
    (net (code "77") (name "unconnected-(SW1-3-Pad4)") (class "Default")
      (node (ref "SW1") (pin "4") (pinfunction "3_4") (pintype "passive"))
    )
    (net (code "78") (name "unconnected-(TC1F-S-Pad5)") (class "Default")
      (node (ref "TC1") (pin "5") (pinfunction "S_5") (pintype "passive"))
    )
    (net (code "79") (name "unconnected-(TC1H-S-Pad7)") (class "Default")
      (node (ref "TC1") (pin "7") (pinfunction "S_7") (pintype "passive"))
    )
    (net (code "80") (name "unconnected-(TC1I-S-Pad8)") (class "Default")
      (node (ref "TC1") (pin "8") (pinfunction "S_8") (pintype "passive"))
    )
  )
)
